# schm.net
KiCad netlist of a schematic drawn in EAGLE
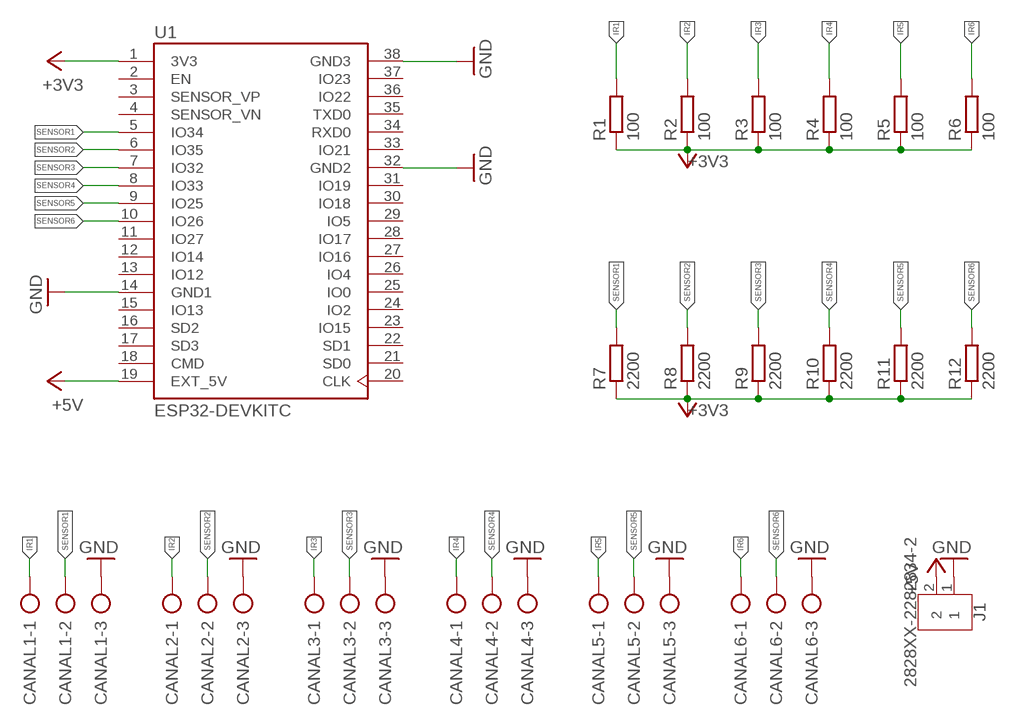
[diagram p0: schematic, sheet 1]

(export (version "E")
  (design (tool "Eeschema 10.0.6"))
  (components
    (comp (ref "CANAL1")
      (value "AK300/3")
      (footprint "eagle-import:AK300_3")
      (libsource (lib "eagle-import") (part "AK300/3"))
    )
    (comp (ref "CANAL2")
      (value "AK300/3")
      (footprint "eagle-import:AK300_3")
      (libsource (lib "eagle-import") (part "AK300/3"))
    )
    (comp (ref "CANAL3")
      (value "AK300/3")
      (footprint "eagle-import:AK300_3")
      (libsource (lib "eagle-import") (part "AK300/3"))
    )
    (comp (ref "CANAL4")
      (value "AK300/3")
      (footprint "eagle-import:AK300_3")
      (libsource (lib "eagle-import") (part "AK300/3"))
    )
    (comp (ref "CANAL5")
      (value "AK300/3")
      (footprint "eagle-import:AK300_3")
      (libsource (lib "eagle-import") (part "AK300/3"))
    )
    (comp (ref "CANAL6")
      (value "AK300/3")
      (footprint "eagle-import:AK300_3")
      (libsource (lib "eagle-import") (part "AK300/3"))
    )
    (comp (ref "J1")
      (value "2828XX-2282834-2")
      (footprint "eagle-import:TERMBLK_254-2N")
      (fields (field (name "MANUFACTURER") "TE Connectivity AMP Connectors") (field (name "MPN") "282834-2 "))
      (libsource (lib "eagle-import") (part "2828XX-2282834-2"))
    )
    (comp (ref "R1")
      (value "100")
      (footprint "eagle-import:0207_10")
      (libsource (lib "eagle-import") (part "R-EU_0207/10"))
    )
    (comp (ref "R2")
      (value "100")
      (footprint "eagle-import:0207_10")
      (libsource (lib "eagle-import") (part "R-EU_0207/10"))
    )
    (comp (ref "R3")
      (value "100")
      (footprint "eagle-import:0207_10")
      (libsource (lib "eagle-import") (part "R-EU_0207/10"))
    )
    (comp (ref "R4")
      (value "100")
      (footprint "eagle-import:0207_10")
      (libsource (lib "eagle-import") (part "R-EU_0207/10"))
    )
    (comp (ref "R5")
      (value "100")
      (footprint "eagle-import:0207_10")
      (libsource (lib "eagle-import") (part "R-EU_0207/10"))
    )
    (comp (ref "R6")
      (value "100")
      (footprint "eagle-import:0207_10")
      (libsource (lib "eagle-import") (part "R-EU_0207/10"))
    )
    (comp (ref "R7")
      (value "2200")
      (footprint "eagle-import:0207_10")
      (libsource (lib "eagle-import") (part "R-EU_0207/10"))
    )
    (comp (ref "R8")
      (value "2200")
      (footprint "eagle-import:0207_10")
      (libsource (lib "eagle-import") (part "R-EU_0207/10"))
    )
    (comp (ref "R9")
      (value "2200")
      (footprint "eagle-import:0207_10")
      (libsource (lib "eagle-import") (part "R-EU_0207/10"))
    )
    (comp (ref "R10")
      (value "2200")
      (footprint "eagle-import:0207_10")
      (libsource (lib "eagle-import") (part "R-EU_0207/10"))
    )
    (comp (ref "R11")
      (value "2200")
      (footprint "eagle-import:0207_10")
      (libsource (lib "eagle-import") (part "R-EU_0207/10"))
    )
    (comp (ref "R12")
      (value "2200")
      (footprint "eagle-import:0207_10")
      (libsource (lib "eagle-import") (part "R-EU_0207/10"))
    )
    (comp (ref "U1")
      (value "ESP32-DEVKITC")
      (footprint "eagle-import:MODULE_ESP32-DEVKITC")
      (fields (field (name "MF") "Espressif Systems") (field (name "MP") "ESP32-DEVKITC-32D-F"))
      (libsource (lib "eagle-import") (part "ESP32-DEVKITC"))
    )
  )
  (nets
    (net (code "1") (name "+3V3") (class "Default")
      (node (ref "R1") (pin "1") (pinfunction "1_1") (pintype "passive"))
      (node (ref "R10") (pin "1") (pinfunction "1_1") (pintype "passive"))
      (node (ref "R11") (pin "1") (pinfunction "1_1") (pintype "passive"))
      (node (ref "R12") (pin "1") (pinfunction "1_1") (pintype "passive"))
      (node (ref "R2") (pin "1") (pinfunction "1_1") (pintype "passive"))
      (node (ref "R3") (pin "1") (pinfunction "1_1") (pintype "passive"))
      (node (ref "R4") (pin "1") (pinfunction "1_1") (pintype "passive"))
      (node (ref "R5") (pin "1") (pinfunction "1_1") (pintype "passive"))
      (node (ref "R6") (pin "1") (pinfunction "1_1") (pintype "passive"))
      (node (ref "R7") (pin "1") (pinfunction "1_1") (pintype "passive"))
      (node (ref "R8") (pin "1") (pinfunction "1_1") (pintype "passive"))
      (node (ref "R9") (pin "1") (pinfunction "1_1") (pintype "passive"))
      (node (ref "U1") (pin "1") (pinfunction "3V3_1") (pintype "power_in"))
    )
    (net (code "2") (name "+5V") (class "Default")
      (node (ref "J1") (pin "2") (pinfunction "2_2") (pintype "bidirectional"))
      (node (ref "U1") (pin "19") (pinfunction "EXT_5V_19") (pintype "power_in"))
    )
    (net (code "3") (name "GND") (class "Default")
      (node (ref "CANAL1") (pin "3") (pinfunction "KL_3") (pintype "passive"))
      (node (ref "CANAL2") (pin "3") (pinfunction "KL_3") (pintype "passive"))
      (node (ref "CANAL3") (pin "3") (pinfunction "KL_3") (pintype "passive"))
      (node (ref "CANAL4") (pin "3") (pinfunction "KL_3") (pintype "passive"))
      (node (ref "CANAL5") (pin "3") (pinfunction "KL_3") (pintype "passive"))
      (node (ref "CANAL6") (pin "3") (pinfunction "KL_3") (pintype "passive"))
      (node (ref "J1") (pin "1") (pinfunction "1_1") (pintype "bidirectional"))
      (node (ref "U1") (pin "14") (pinfunction "GND1_14") (pintype "power_in"))
      (node (ref "U1") (pin "32") (pinfunction "GND2_32") (pintype "power_in"))
      (node (ref "U1") (pin "38") (pinfunction "GND3_38") (pintype "power_in"))
    )
    (net (code "4") (name "IR1") (class "Default")
      (node (ref "CANAL1") (pin "1") (pinfunction "KL_1") (pintype "passive"))
      (node (ref "R1") (pin "2") (pinfunction "2_2") (pintype "passive"))
    )
    (net (code "5") (name "IR2") (class "Default")
      (node (ref "CANAL2") (pin "1") (pinfunction "KL_1") (pintype "passive"))
      (node (ref "R2") (pin "2") (pinfunction "2_2") (pintype "passive"))
    )
    (net (code "6") (name "IR3") (class "Default")
      (node (ref "CANAL3") (pin "1") (pinfunction "KL_1") (pintype "passive"))
      (node (ref "R3") (pin "2") (pinfunction "2_2") (pintype "passive"))
    )
    (net (code "7") (name "IR4") (class "Default")
      (node (ref "CANAL4") (pin "1") (pinfunction "KL_1") (pintype "passive"))
      (node (ref "R4") (pin "2") (pinfunction "2_2") (pintype "passive"))
    )
    (net (code "8") (name "IR5") (class "Default")
      (node (ref "CANAL5") (pin "1") (pinfunction "KL_1") (pintype "passive"))
      (node (ref "R5") (pin "2") (pinfunction "2_2") (pintype "passive"))
    )
    (net (code "9") (name "IR6") (class "Default")
      (node (ref "CANAL6") (pin "1") (pinfunction "KL_1") (pintype "passive"))
      (node (ref "R6") (pin "2") (pinfunction "2_2") (pintype "passive"))
    )
    (net (code "10") (name "SENSOR1") (class "Default")
      (node (ref "CANAL1") (pin "2") (pinfunction "KL_2") (pintype "passive"))
      (node (ref "R7") (pin "2") (pinfunction "2_2") (pintype "passive"))
      (node (ref "U1") (pin "5") (pinfunction "IO34_5") (pintype "bidirectional"))
    )
    (net (code "11") (name "SENSOR2") (class "Default")
      (node (ref "CANAL2") (pin "2") (pinfunction "KL_2") (pintype "passive"))
      (node (ref "R8") (pin "2") (pinfunction "2_2") (pintype "passive"))
      (node (ref "U1") (pin "6") (pinfunction "IO35_6") (pintype "bidirectional"))
    )
    (net (code "12") (name "SENSOR3") (class "Default")
      (node (ref "CANAL3") (pin "2") (pinfunction "KL_2") (pintype "passive"))
      (node (ref "R9") (pin "2") (pinfunction "2_2") (pintype "passive"))
      (node (ref "U1") (pin "7") (pinfunction "IO32_7") (pintype "bidirectional"))
    )
    (net (code "13") (name "SENSOR4") (class "Default")
      (node (ref "CANAL4") (pin "2") (pinfunction "KL_2") (pintype "passive"))
      (node (ref "R10") (pin "2") (pinfunction "2_2") (pintype "passive"))
      (node (ref "U1") (pin "8") (pinfunction "IO33_8") (pintype "bidirectional"))
    )
    (net (code "14") (name "SENSOR5") (class "Default")
      (node (ref "CANAL5") (pin "2") (pinfunction "KL_2") (pintype "passive"))
      (node (ref "R11") (pin "2") (pinfunction "2_2") (pintype "passive"))
      (node (ref "U1") (pin "9") (pinfunction "IO25_9") (pintype "bidirectional"))
    )
    (net (code "15") (name "SENSOR6") (class "Default")
      (node (ref "CANAL6") (pin "2") (pinfunction "KL_2") (pintype "passive"))
      (node (ref "R12") (pin "2") (pinfunction "2_2") (pintype "passive"))
      (node (ref "U1") (pin "10") (pinfunction "IO26_10") (pintype "bidirectional"))
    )
    (net (code "16") (name "unconnected-(U1-CLK-Pad20)") (class "Default")
      (node (ref "U1") (pin "20") (pinfunction "CLK_20") (pintype "input"))
    )
    (net (code "17") (name "unconnected-(U1-CMD-Pad18)") (class "Default")
      (node (ref "U1") (pin "18") (pinfunction "CMD_18") (pintype "bidirectional"))
    )
    (net (code "18") (name "unconnected-(U1-EN-Pad2)") (class "Default")
      (node (ref "U1") (pin "2") (pinfunction "EN_2") (pintype "input"))
    )
    (net (code "19") (name "unconnected-(U1-IO0-Pad25)") (class "Default")
      (node (ref "U1") (pin "25") (pinfunction "IO0_25") (pintype "bidirectional"))
    )
    (net (code "20") (name "unconnected-(U1-IO2-Pad24)") (class "Default")
      (node (ref "U1") (pin "24") (pinfunction "IO2_24") (pintype "bidirectional"))
    )
    (net (code "21") (name "unconnected-(U1-IO4-Pad26)") (class "Default")
      (node (ref "U1") (pin "26") (pinfunction "IO4_26") (pintype "bidirectional"))
    )
    (net (code "22") (name "unconnected-(U1-IO5-Pad29)") (class "Default")
      (node (ref "U1") (pin "29") (pinfunction "IO5_29") (pintype "bidirectional"))
    )
    (net (code "23") (name "unconnected-(U1-IO12-Pad13)") (class "Default")
      (node (ref "U1") (pin "13") (pinfunction "IO12_13") (pintype "bidirectional"))
    )
    (net (code "24") (name "unconnected-(U1-IO13-Pad15)") (class "Default")
      (node (ref "U1") (pin "15") (pinfunction "IO13_15") (pintype "bidirectional"))
    )
    (net (code "25") (name "unconnected-(U1-IO14-Pad12)") (class "Default")
      (node (ref "U1") (pin "12") (pinfunction "IO14_12") (pintype "bidirectional"))
    )
    (net (code "26") (name "unconnected-(U1-IO15-Pad23)") (class "Default")
      (node (ref "U1") (pin "23") (pinfunction "IO15_23") (pintype "bidirectional"))
    )
    (net (code "27") (name "unconnected-(U1-IO16-Pad27)") (class "Default")
      (node (ref "U1") (pin "27") (pinfunction "IO16_27") (pintype "bidirectional"))
    )
    (net (code "28") (name "unconnected-(U1-IO17-Pad28)") (class "Default")
      (node (ref "U1") (pin "28") (pinfunction "IO17_28") (pintype "bidirectional"))
    )
    (net (code "29") (name "unconnected-(U1-IO18-Pad30)") (class "Default")
      (node (ref "U1") (pin "30") (pinfunction "IO18_30") (pintype "bidirectional"))
    )
    (net (code "30") (name "unconnected-(U1-IO19-Pad31)") (class "Default")
      (node (ref "U1") (pin "31") (pinfunction "IO19_31") (pintype "bidirectional"))
    )
    (net (code "31") (name "unconnected-(U1-IO21-Pad33)") (class "Default")
      (node (ref "U1") (pin "33") (pinfunction "IO21_33") (pintype "bidirectional"))
    )
    (net (code "32") (name "unconnected-(U1-IO22-Pad36)") (class "Default")
      (node (ref "U1") (pin "36") (pinfunction "IO22_36") (pintype "bidirectional"))
    )
    (net (code "33") (name "unconnected-(U1-IO23-Pad37)") (class "Default")
      (node (ref "U1") (pin "37") (pinfunction "IO23_37") (pintype "bidirectional"))
    )
    (net (code "34") (name "unconnected-(U1-IO27-Pad11)") (class "Default")
      (node (ref "U1") (pin "11") (pinfunction "IO27_11") (pintype "bidirectional"))
    )
    (net (code "35") (name "unconnected-(U1-RXD0-Pad34)") (class "Default")
      (node (ref "U1") (pin "34") (pinfunction "RXD0_34") (pintype "input"))
    )
    (net (code "36") (name "unconnected-(U1-SD0-Pad21)") (class "Default")
      (node (ref "U1") (pin "21") (pinfunction "SD0_21") (pintype "bidirectional"))
    )
    (net (code "37") (name "unconnected-(U1-SD1-Pad22)") (class "Default")
      (node (ref "U1") (pin "22") (pinfunction "SD1_22") (pintype "bidirectional"))
    )
    (net (code "38") (name "unconnected-(U1-SD2-Pad16)") (class "Default")
      (node (ref "U1") (pin "16") (pinfunction "SD2_16") (pintype "bidirectional"))
    )
    (net (code "39") (name "unconnected-(U1-SD3-Pad17)") (class "Default")
      (node (ref "U1") (pin "17") (pinfunction "SD3_17") (pintype "bidirectional"))
    )
    (net (code "40") (name "unconnected-(U1-SENSOR_VN-Pad4)") (class "Default")
      (node (ref "U1") (pin "4") (pinfunction "SENSOR_VN_4") (pintype "input"))
    )
    (net (code "41") (name "unconnected-(U1-SENSOR_VP-Pad3)") (class "Default")
      (node (ref "U1") (pin "3") (pinfunction "SENSOR_VP_3") (pintype "input"))
    )
    (net (code "42") (name "unconnected-(U1-TXD0-Pad35)") (class "Default")
      (node (ref "U1") (pin "35") (pinfunction "TXD0_35") (pintype "output"))
    )
  )
)
